# Motorschutz_MC33926.net
KiCad netlist of a schematic drawn in EAGLE
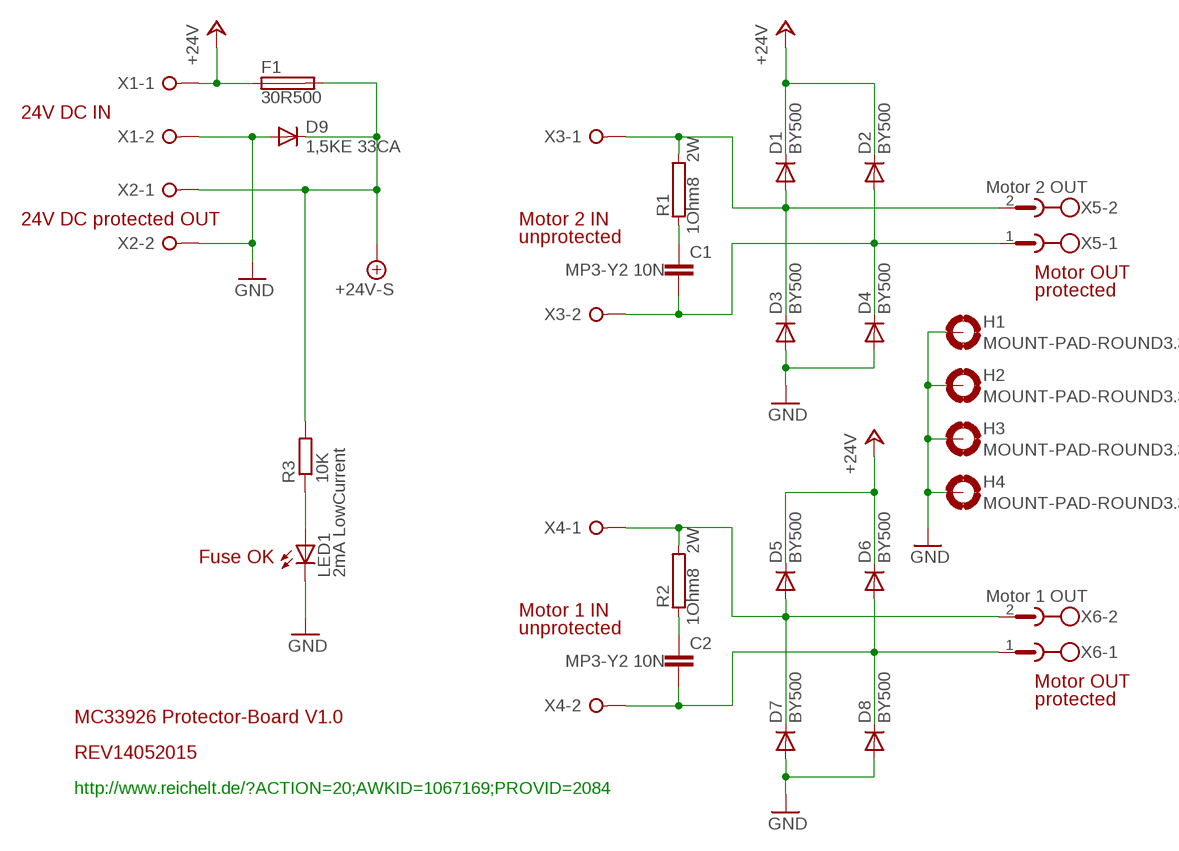
[diagram p0: schematic, sheet 1]

(export (version "E")
  (design (tool "Eeschema 10.0.6"))
  (components
    (comp (ref "C1")
      (value "MP3-Y2 10N")
      (footprint "eagle-import:C15B5")
      (libsource (lib "eagle-import") (part "C15/5"))
    )
    (comp (ref "C2")
      (value "MP3-Y2 10N")
      (footprint "eagle-import:C15B5")
      (libsource (lib "eagle-import") (part "C15/5"))
    )
    (comp (ref "D1")
      (value "BY500")
      (footprint "eagle-import:DO201-15")
      (libsource (lib "eagle-import") (part "BY500"))
    )
    (comp (ref "D2")
      (value "BY500")
      (footprint "eagle-import:DO201-15")
      (libsource (lib "eagle-import") (part "BY500"))
    )
    (comp (ref "D3")
      (value "BY500")
      (footprint "eagle-import:DO201-15")
      (libsource (lib "eagle-import") (part "BY500"))
    )
    (comp (ref "D4")
      (value "BY500")
      (footprint "eagle-import:DO201-15")
      (libsource (lib "eagle-import") (part "BY500"))
    )
    (comp (ref "D5")
      (value "BY500")
      (footprint "eagle-import:DO201-15")
      (libsource (lib "eagle-import") (part "BY500"))
    )
    (comp (ref "D6")
      (value "BY500")
      (footprint "eagle-import:DO201-15")
      (libsource (lib "eagle-import") (part "BY500"))
    )
    (comp (ref "D7")
      (value "BY500")
      (footprint "eagle-import:DO201-15")
      (libsource (lib "eagle-import") (part "BY500"))
    )
    (comp (ref "D8")
      (value "BY500")
      (footprint "eagle-import:DO201-15")
      (libsource (lib "eagle-import") (part "BY500"))
    )
    (comp (ref "D9")
      (value "1,5KE 33CA")
      (footprint "eagle-import:DO201-15")
      (libsource (lib "eagle-import") (part "BY500"))
    )
    (comp (ref "F1")
      (value "30R500")
      (footprint "eagle-import:LITTLEFUSE")
      (libsource (lib "eagle-import") (part "LITTLEFUSE"))
    )
    (comp (ref "H1")
      (value "MOUNT-PAD-ROUND3.3")
      (footprint "eagle-import:3,3-PAD")
      (libsource (lib "eagle-import") (part "MOUNT-PAD-ROUND3.3"))
    )
    (comp (ref "H2")
      (value "MOUNT-PAD-ROUND3.3")
      (footprint "eagle-import:3,3-PAD")
      (libsource (lib "eagle-import") (part "MOUNT-PAD-ROUND3.3"))
    )
    (comp (ref "H3")
      (value "MOUNT-PAD-ROUND3.3")
      (footprint "eagle-import:3,3-PAD")
      (libsource (lib "eagle-import") (part "MOUNT-PAD-ROUND3.3"))
    )
    (comp (ref "H4")
      (value "MOUNT-PAD-ROUND3.3")
      (footprint "eagle-import:3,3-PAD")
      (libsource (lib "eagle-import") (part "MOUNT-PAD-ROUND3.3"))
    )
    (comp (ref "LED1")
      (value "2mA LowCurrent")
      (footprint "eagle-import:LED5MM")
      (libsource (lib "eagle-import") (part "LED5MM"))
    )
    (comp (ref "R1")
      (value "1Ohm8 2W")
      (footprint "eagle-import:AC07")
      (libsource (lib "eagle-import") (part "RAC07"))
    )
    (comp (ref "R2")
      (value "1Ohm8 2W")
      (footprint "eagle-import:AC07")
      (libsource (lib "eagle-import") (part "RAC07"))
    )
    (comp (ref "R3")
      (value "10K")
      (footprint "eagle-import:0204_7")
      (libsource (lib "eagle-import") (part "R-EU_0204/7"))
    )
    (comp (ref "X1")
      (value "W237-02P")
      (footprint "eagle-import:W237-132")
      (libsource (lib "eagle-import") (part "W237-02P"))
    )
    (comp (ref "X2")
      (value "W237-02P")
      (footprint "eagle-import:W237-132")
      (libsource (lib "eagle-import") (part "W237-02P"))
    )
    (comp (ref "X3")
      (value "W237-02P")
      (footprint "eagle-import:W237-132")
      (libsource (lib "eagle-import") (part "W237-02P"))
    )
    (comp (ref "X4")
      (value "W237-02P")
      (footprint "eagle-import:W237-132")
      (libsource (lib "eagle-import") (part "W237-02P"))
    )
    (comp (ref "X5")
      (value "Motor 2 OUT")
      (footprint "eagle-import:MSTBV2")
      (fields (field (name "MPN") "MSTBV 2,5/2-GF-5.08"))
      (libsource (lib "eagle-import") (part "MSTBV2"))
    )
    (comp (ref "X6")
      (value "Motor 1 OUT")
      (footprint "eagle-import:MSTBV2")
      (fields (field (name "MPN") "MSTBV 2,5/2-GF-5.08"))
      (libsource (lib "eagle-import") (part "MSTBV2"))
    )
  )
  (nets
    (net (code "1") (name "+24V") (class "Default")
      (node (ref "D1") (pin "C") (pinfunction "C_C") (pintype "passive"))
      (node (ref "D2") (pin "C") (pinfunction "C_C") (pintype "passive"))
      (node (ref "D5") (pin "C") (pinfunction "C_C") (pintype "passive"))
      (node (ref "D6") (pin "C") (pinfunction "C_C") (pintype "passive"))
      (node (ref "F1") (pin "1") (pinfunction "1_1") (pintype "passive"))
      (node (ref "X1") (pin "1") (pinfunction "KL_1") (pintype "passive"))
    )
    (net (code "2") (name "+24V-S") (class "Default")
      (node (ref "D9") (pin "C") (pinfunction "C_C") (pintype "passive"))
      (node (ref "F1") (pin "2") (pinfunction "2_2") (pintype "passive"))
      (node (ref "R3") (pin "2") (pinfunction "2_2") (pintype "passive"))
      (node (ref "X2") (pin "1") (pinfunction "KL_1") (pintype "passive"))
    )
    (net (code "3") (name "GND") (class "Default")
      (node (ref "D3") (pin "A") (pinfunction "A_A") (pintype "passive"))
      (node (ref "D4") (pin "A") (pinfunction "A_A") (pintype "passive"))
      (node (ref "D7") (pin "A") (pinfunction "A_A") (pintype "passive"))
      (node (ref "D8") (pin "A") (pinfunction "A_A") (pintype "passive"))
      (node (ref "D9") (pin "A") (pinfunction "A_A") (pintype "passive"))
      (node (ref "H1") (pin "B3,3") (pinfunction "MOUNT_B3,3") (pintype "passive"))
      (node (ref "H2") (pin "B3,3") (pinfunction "MOUNT_B3,3") (pintype "passive"))
      (node (ref "H3") (pin "B3,3") (pinfunction "MOUNT_B3,3") (pintype "passive"))
      (node (ref "H4") (pin "B3,3") (pinfunction "MOUNT_B3,3") (pintype "passive"))
      (node (ref "LED1") (pin "K") (pinfunction "C_K") (pintype "passive"))
      (node (ref "X1") (pin "2") (pinfunction "KL_2") (pintype "passive"))
      (node (ref "X2") (pin "2") (pinfunction "KL_2") (pintype "passive"))
    )
    (net (code "4") (name "Net-(C1-Pad1)") (class "Default")
      (node (ref "C1") (pin "1") (pinfunction "1_1") (pintype "passive"))
      (node (ref "R1") (pin "1") (pinfunction "1_1") (pintype "passive"))
    )
    (net (code "5") (name "Net-(C2-Pad1)") (class "Default")
      (node (ref "C2") (pin "1") (pinfunction "1_1") (pintype "passive"))
      (node (ref "R2") (pin "1") (pinfunction "1_1") (pintype "passive"))
    )
    (net (code "6") (name "Net-(LED1-PadA)") (class "Default")
      (node (ref "LED1") (pin "A") (pinfunction "A_A") (pintype "passive"))
      (node (ref "R3") (pin "1") (pinfunction "1_1") (pintype "passive"))
    )
    (net (code "7") (name "Net-(X3A-KL)") (class "Default")
      (node (ref "D1") (pin "A") (pinfunction "A_A") (pintype "passive"))
      (node (ref "D3") (pin "C") (pinfunction "C_C") (pintype "passive"))
      (node (ref "R1") (pin "2") (pinfunction "2_2") (pintype "passive"))
      (node (ref "X3") (pin "1") (pinfunction "KL_1") (pintype "passive"))
      (node (ref "X5") (pin "2") (pinfunction "1_2") (pintype "passive"))
    )
    (net (code "8") (name "Net-(X3B-KL)") (class "Default")
      (node (ref "C1") (pin "2") (pinfunction "2_2") (pintype "passive"))
      (node (ref "D2") (pin "A") (pinfunction "A_A") (pintype "passive"))
      (node (ref "D4") (pin "C") (pinfunction "C_C") (pintype "passive"))
      (node (ref "X3") (pin "2") (pinfunction "KL_2") (pintype "passive"))
      (node (ref "X5") (pin "1") (pinfunction "1_1") (pintype "passive"))
    )
    (net (code "9") (name "Net-(X4A-KL)") (class "Default")
      (node (ref "D5") (pin "A") (pinfunction "A_A") (pintype "passive"))
      (node (ref "D7") (pin "C") (pinfunction "C_C") (pintype "passive"))
      (node (ref "R2") (pin "2") (pinfunction "2_2") (pintype "passive"))
      (node (ref "X4") (pin "1") (pinfunction "KL_1") (pintype "passive"))
      (node (ref "X6") (pin "2") (pinfunction "1_2") (pintype "passive"))
    )
    (net (code "10") (name "Net-(X4B-KL)") (class "Default")
      (node (ref "C2") (pin "2") (pinfunction "2_2") (pintype "passive"))
      (node (ref "D6") (pin "A") (pinfunction "A_A") (pintype "passive"))
      (node (ref "D8") (pin "C") (pinfunction "C_C") (pintype "passive"))
      (node (ref "X4") (pin "2") (pinfunction "KL_2") (pintype "passive"))
      (node (ref "X6") (pin "1") (pinfunction "1_1") (pintype "passive"))
    )
  )
)
